# Sheet1.net
KiCad netlist of a schematic drawn in Altium Designer
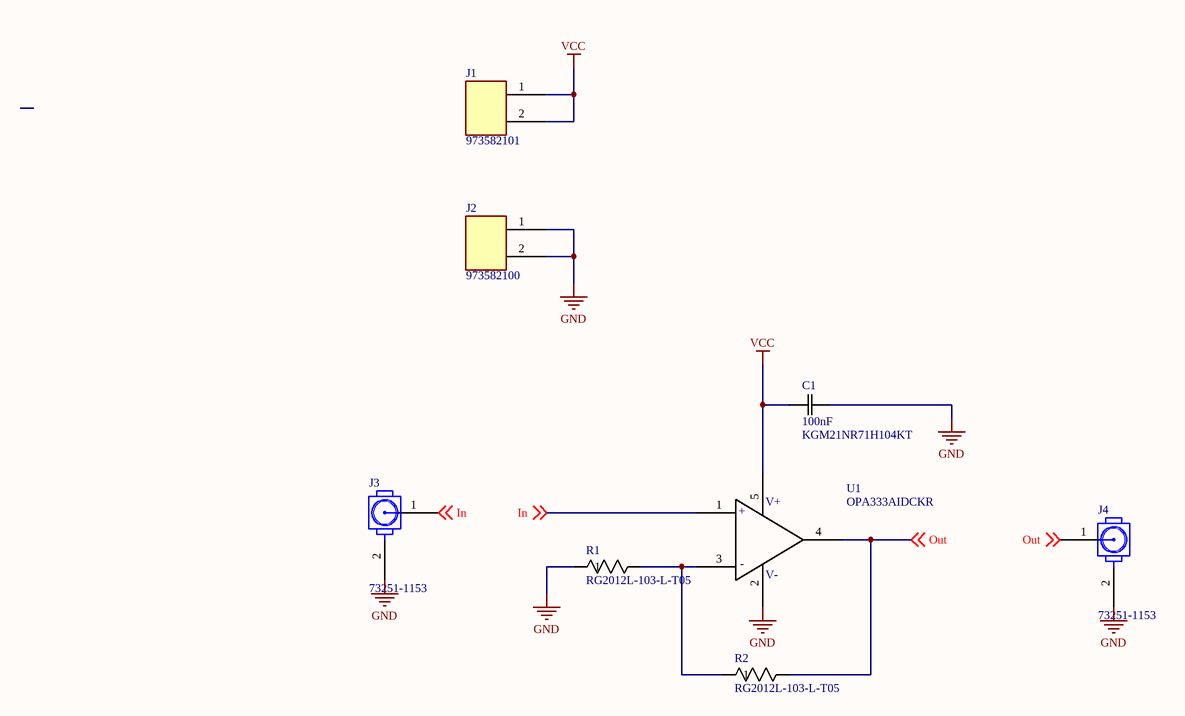
[diagram p0: Sheet1.SchDoc]

(export (version "E")
  (design (tool "Eeschema 10.0.6"))
  (components
    (comp (ref "C1")
      (value "KGM21NR71H104KT")
      (footprint "CAP_KGM21_KAV")
      (description "CAP CER 100nF")
      (fields (field (name "ALTIUM_VALUE") "100nF"))
      (libsource (lib "Schlib1") (part "CAP_100nF_0805_SMD"))
    )
    (comp (ref "J1")
      (value "973582101")
      (footprint "CON_973582101_Red")
      (description "Red Banana Connector")
      (fields (field (name "MANUFACTURER") "Altech Corp"))
      (libsource (lib "Schlib1") (part "CON_973582101_Red"))
    )
    (comp (ref "J2")
      (value "973582100")
      (footprint "CON_973582100_Black")
      (description "Black Banana Connector")
      (fields (field (name "MANUFACTURER") "Altech Corp"))
      (libsource (lib "Schlib1") (part "CON_973582100"))
    )
    (comp (ref "J3")
      (value "73251-1153")
      (footprint "73251-1153")
      (description "SMA Connector")
      (fields (field (name "MANUFACTURER") "Molex"))
      (libsource (lib "Schlib1") (part "73251-1153"))
    )
    (comp (ref "J4")
      (value "73251-1153")
      (footprint "73251-1153")
      (description "SMA Connector")
      (fields (field (name "MANUFACTURER") "Molex"))
      (libsource (lib "") (part "73251-1153_1"))
    )
    (comp (ref "R1")
      (value "RG2012L-103-L-T05")
      (footprint "RES_1220_SUS")
      (description "Resistor 10k Ohm 0805 SMD")
      (libsource (lib "Schlib1") (part "RES_10k_0805_SMD"))
    )
    (comp (ref "R2")
      (value "RG2012L-103-L-T05")
      (footprint "RES_1220_SUS")
      (description "Resistor 10k Ohm 0805 SMD")
      (libsource (lib "Schlib1") (part "RES_10k_0805_SMD"))
    )
    (comp (ref "U1")
      (value "OPA333AIDCKR")
      (footprint "SC70+5_0.95X0.4_0.65_SMD")
      (description "OP Amp")
      (fields (field (name "MANUFACTURER") "TI"))
      (libsource (lib "Schlib1") (part "IC_OPA333AIDCKR"))
    )
  )
  (nets
    (net (code "1") (name "GND") (class "Default")
      (node (ref "C1") (pin "2") (pinfunction "2_2") (pintype "passive"))
      (node (ref "J2") (pin "1") (pinfunction "1_1") (pintype "passive"))
      (node (ref "J2") (pin "2") (pinfunction "2_2") (pintype "passive"))
      (node (ref "J3") (pin "2") (pinfunction "2_2") (pintype "passive"))
      (node (ref "J4") (pin "2") (pinfunction "2_2") (pintype "passive"))
      (node (ref "R1") (pin "1") (pinfunction "1_1") (pintype "passive"))
      (node (ref "U1") (pin "2") (pinfunction "V-_2") (pintype "passive"))
    )
    (net (code "2") (name "In") (class "Default")
      (node (ref "J3") (pin "1") (pinfunction "1_1") (pintype "passive"))
      (node (ref "U1") (pin "1") (pinfunction "+IN_1") (pintype "passive"))
    )
    (net (code "3") (name "Net-(U1--IN)") (class "Default")
      (node (ref "R1") (pin "2") (pinfunction "2_2") (pintype "passive"))
      (node (ref "R2") (pin "1") (pinfunction "1_1") (pintype "passive"))
      (node (ref "U1") (pin "3") (pinfunction "-IN_3") (pintype "passive"))
    )
    (net (code "4") (name "Out") (class "Default")
      (node (ref "J4") (pin "1") (pinfunction "1_1") (pintype "passive"))
      (node (ref "R2") (pin "2") (pinfunction "2_2") (pintype "passive"))
      (node (ref "U1") (pin "4") (pinfunction "OUT_4") (pintype "passive"))
    )
    (net (code "5") (name "VCC") (class "Default")
      (node (ref "C1") (pin "1") (pinfunction "1_1") (pintype "passive"))
      (node (ref "J1") (pin "1") (pinfunction "1_1") (pintype "passive"))
      (node (ref "J1") (pin "2") (pinfunction "2_2") (pintype "passive"))
      (node (ref "U1") (pin "5") (pinfunction "V+_5") (pintype "passive"))
    )
  )
)
